# Detector.net
KiCad netlist of a schematic drawn in Altium Designer
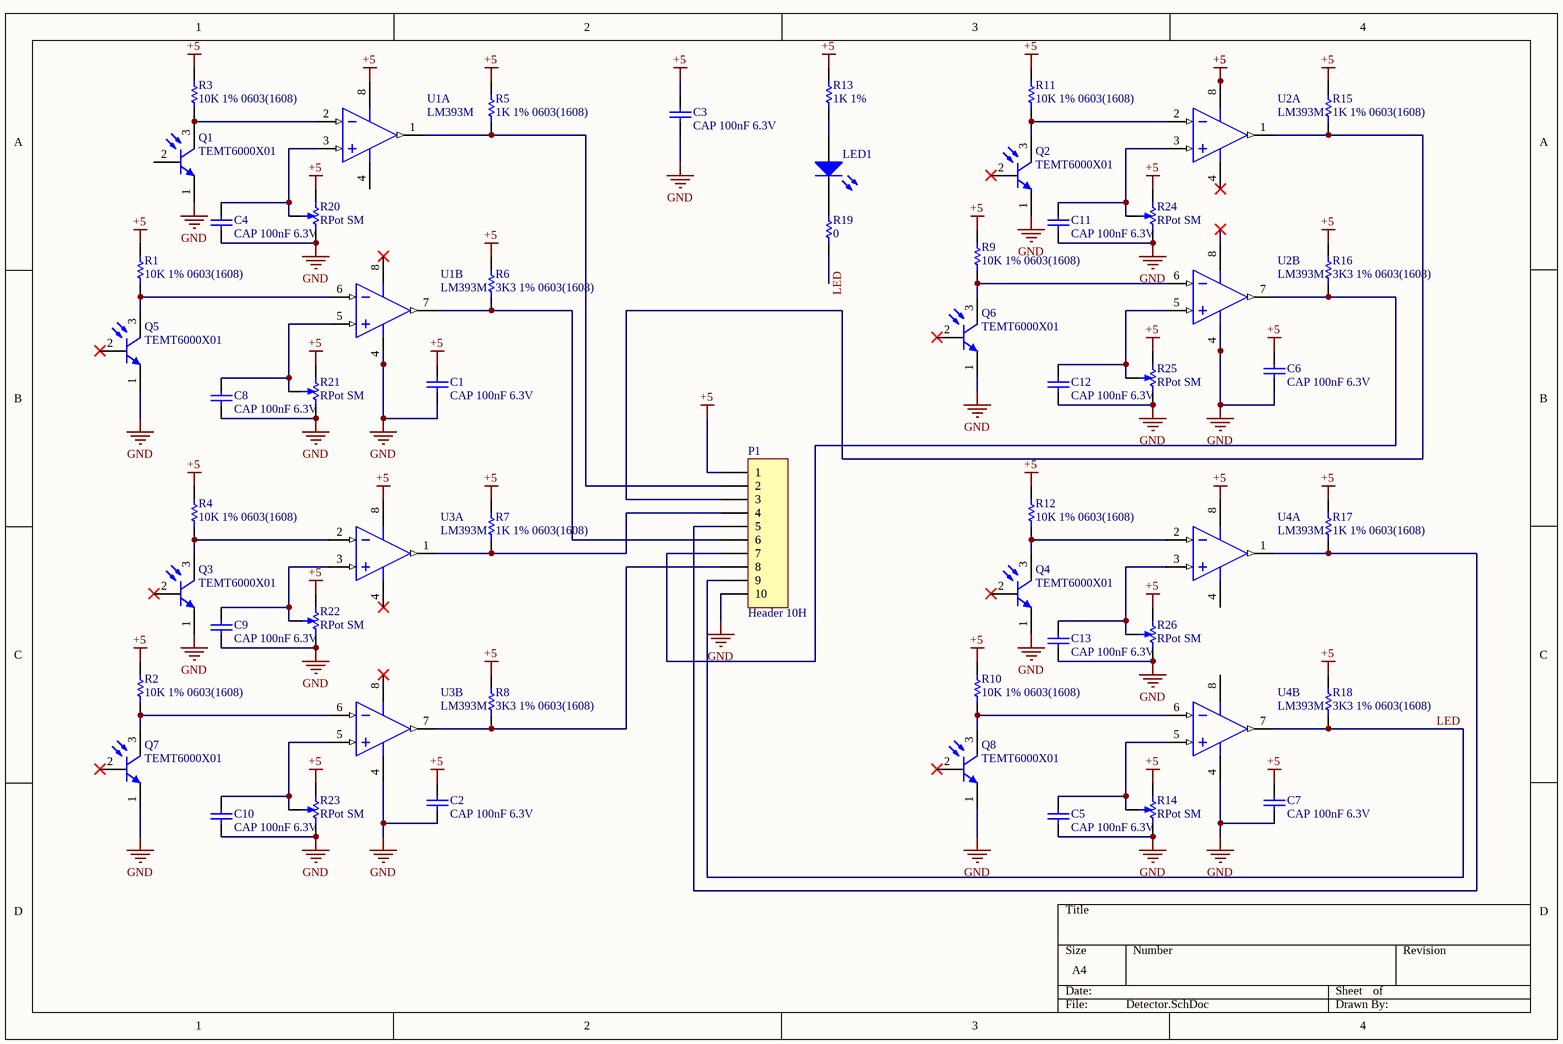
[diagram p0: Detector.SchDoc]

(export (version "E")
  (design (tool "Eeschema 10.0.6"))
  (components
    (comp (ref "C1")
      (value "CAP 100nF 6.3V")
      (footprint "CAPC0603(1608)100_N")
      (description "CAP 100nF 6.3V ±10% 0603 (1608 Metric) Thickness 1mm SMD")
      (fields (field (name "TOLERANCE") "Â±10%"))
      (libsource (lib "Altium Content Vault") (part "CAP"))
    )
    (comp (ref "C2")
      (value "CAP 100nF 6.3V")
      (footprint "CAPC0603(1608)100_N")
      (description "CAP 100nF 6.3V ±10% 0603 (1608 Metric) Thickness 1mm SMD")
      (fields (field (name "TOLERANCE") "Â±10%"))
      (libsource (lib "Altium Content Vault") (part "CAP"))
    )
    (comp (ref "C3")
      (value "CAP 100nF 6.3V")
      (footprint "CAPC0603(1608)100_N")
      (description "CAP 100nF 6.3V ±10% 0603 (1608 Metric) Thickness 1mm SMD")
      (fields (field (name "TOLERANCE") "Â±10%"))
      (libsource (lib "Altium Content Vault") (part "CAP"))
    )
    (comp (ref "C4")
      (value "CAP 100nF 6.3V")
      (footprint "CAPC0603(1608)100_N")
      (description "CAP 100nF 6.3V ±10% 0603 (1608 Metric) Thickness 1mm SMD")
      (fields (field (name "TOLERANCE") "Â±10%"))
      (libsource (lib "Altium Content Vault") (part "CAP"))
    )
    (comp (ref "C5")
      (value "CAP 100nF 6.3V")
      (footprint "CAPC0603(1608)100_N")
      (description "CAP 100nF 6.3V ±10% 0603 (1608 Metric) Thickness 1mm SMD")
      (fields (field (name "TOLERANCE") "Â±10%"))
      (libsource (lib "Altium Content Vault") (part "CAP"))
    )
    (comp (ref "C6")
      (value "CAP 100nF 6.3V")
      (footprint "CAPC0603(1608)100_N")
      (description "CAP 100nF 6.3V ±10% 0603 (1608 Metric) Thickness 1mm SMD")
      (fields (field (name "TOLERANCE") "Â±10%"))
      (libsource (lib "Altium Content Vault") (part "CAP"))
    )
    (comp (ref "C7")
      (value "CAP 100nF 6.3V")
      (footprint "CAPC0603(1608)100_N")
      (description "CAP 100nF 6.3V ±10% 0603 (1608 Metric) Thickness 1mm SMD")
      (fields (field (name "TOLERANCE") "Â±10%"))
      (libsource (lib "Altium Content Vault") (part "CAP"))
    )
    (comp (ref "C8")
      (value "CAP 100nF 6.3V")
      (footprint "CAPC0603(1608)100_N")
      (description "CAP 100nF 6.3V ±10% 0603 (1608 Metric) Thickness 1mm SMD")
      (fields (field (name "TOLERANCE") "Â±10%"))
      (libsource (lib "Altium Content Vault") (part "CAP"))
    )
    (comp (ref "C9")
      (value "CAP 100nF 6.3V")
      (footprint "CAPC0603(1608)100_N")
      (description "CAP 100nF 6.3V ±10% 0603 (1608 Metric) Thickness 1mm SMD")
      (fields (field (name "TOLERANCE") "Â±10%"))
      (libsource (lib "Altium Content Vault") (part "CAP"))
    )
    (comp (ref "C10")
      (value "CAP 100nF 6.3V")
      (footprint "CAPC0603(1608)100_N")
      (description "CAP 100nF 6.3V ±10% 0603 (1608 Metric) Thickness 1mm SMD")
      (fields (field (name "TOLERANCE") "Â±10%"))
      (libsource (lib "Altium Content Vault") (part "CAP"))
    )
    (comp (ref "C11")
      (value "CAP 100nF 6.3V")
      (footprint "CAPC0603(1608)100_N")
      (description "CAP 100nF 6.3V ±10% 0603 (1608 Metric) Thickness 1mm SMD")
      (fields (field (name "TOLERANCE") "Â±10%"))
      (libsource (lib "Altium Content Vault") (part "CAP"))
    )
    (comp (ref "C12")
      (value "CAP 100nF 6.3V")
      (footprint "CAPC0603(1608)100_N")
      (description "CAP 100nF 6.3V ±10% 0603 (1608 Metric) Thickness 1mm SMD")
      (fields (field (name "TOLERANCE") "Â±10%"))
      (libsource (lib "Altium Content Vault") (part "CAP"))
    )
    (comp (ref "C13")
      (value "CAP 100nF 6.3V")
      (footprint "CAPC0603(1608)100_N")
      (description "CAP 100nF 6.3V ±10% 0603 (1608 Metric) Thickness 1mm SMD")
      (fields (field (name "TOLERANCE") "Â±10%"))
      (libsource (lib "Altium Content Vault") (part "CAP"))
    )
    (comp (ref "LED1")
      (value "150060BS75000")
      (footprint "0603_A")
      (description "SMD mono-color Chip LED, WL-SMCW, Blue")
      (fields (field (name "MANUFACTURER") "Wuerth Elektronik"))
      (libsource (lib "Altium Content Vault") (part "WE-LED_K1A2-2"))
    )
    (comp (ref "P1")
      (value "Header 10H")
      (footprint "HDR1X10H")
      (description "Header, 10-Pin, Right Angle")
      (fields (field (name "PUBLISHER") "Altium Limited"))
      (libsource (lib "Miscellaneous Connectors") (part "Header 10H"))
    )
    (comp (ref "Q1")
      (value "TEMT6000X01")
      (footprint "VSIL-TEMT6000X01_V")
      (description "Ambient Light Sensor\r\n, 100 mW, -40 to 100 degC, 3-Pin SMD, RoHS, Tape and Reel")
      (libsource (lib "Altium Content Vault") (part "PHOTO-NPN-EBC-3"))
    )
    (comp (ref "Q2")
      (value "TEMT6000X01")
      (footprint "VSIL-TEMT6000X01_V")
      (description "Ambient Light Sensor\r\n, 100 mW, -40 to 100 degC, 3-Pin SMD, RoHS, Tape and Reel")
      (libsource (lib "Altium Content Vault") (part "PHOTO-NPN-EBC-3"))
    )
    (comp (ref "Q3")
      (value "TEMT6000X01")
      (footprint "VSIL-TEMT6000X01_V")
      (description "Ambient Light Sensor\r\n, 100 mW, -40 to 100 degC, 3-Pin SMD, RoHS, Tape and Reel")
      (libsource (lib "Altium Content Vault") (part "PHOTO-NPN-EBC-3"))
    )
    (comp (ref "Q4")
      (value "TEMT6000X01")
      (footprint "VSIL-TEMT6000X01_V")
      (description "Ambient Light Sensor\r\n, 100 mW, -40 to 100 degC, 3-Pin SMD, RoHS, Tape and Reel")
      (libsource (lib "Altium Content Vault") (part "PHOTO-NPN-EBC-3"))
    )
    (comp (ref "Q5")
      (value "TEMT6000X01")
      (footprint "VSIL-TEMT6000X01_V")
      (description "Ambient Light Sensor\r\n, 100 mW, -40 to 100 degC, 3-Pin SMD, RoHS, Tape and Reel")
      (libsource (lib "Altium Content Vault") (part "PHOTO-NPN-EBC-3"))
    )
    (comp (ref "Q6")
      (value "TEMT6000X01")
      (footprint "VSIL-TEMT6000X01_V")
      (description "Ambient Light Sensor\r\n, 100 mW, -40 to 100 degC, 3-Pin SMD, RoHS, Tape and Reel")
      (libsource (lib "Altium Content Vault") (part "PHOTO-NPN-EBC-3"))
    )
    (comp (ref "Q7")
      (value "TEMT6000X01")
      (footprint "VSIL-TEMT6000X01_V")
      (description "Ambient Light Sensor\r\n, 100 mW, -40 to 100 degC, 3-Pin SMD, RoHS, Tape and Reel")
      (libsource (lib "Altium Content Vault") (part "PHOTO-NPN-EBC-3"))
    )
    (comp (ref "Q8")
      (value "TEMT6000X01")
      (footprint "VSIL-TEMT6000X01_V")
      (description "Ambient Light Sensor\r\n, 100 mW, -40 to 100 degC, 3-Pin SMD, RoHS, Tape and Reel")
      (libsource (lib "Altium Content Vault") (part "PHOTO-NPN-EBC-3"))
    )
    (comp (ref "R1")
      (value "10K 1% 0603(1608)")
      (footprint "RESC0603(1608)_N")
      (description "10K 0.1W 1% 0603 (1608 Metric)  SMD")
      (fields (field (name "POWER") "0.1 W") (field (name "TOLERANCE") "1 %"))
      (libsource (lib "Altium Content Vault") (part "RES"))
    )
    (comp (ref "R2")
      (value "10K 1% 0603(1608)")
      (footprint "RESC0603(1608)_N")
      (description "10K 0.1W 1% 0603 (1608 Metric)  SMD")
      (fields (field (name "POWER") "0.1 W") (field (name "TOLERANCE") "1 %"))
      (libsource (lib "Altium Content Vault") (part "RES"))
    )
    (comp (ref "R3")
      (value "10K 1% 0603(1608)")
      (footprint "RESC0603(1608)_N")
      (description "10K 0.1W 1% 0603 (1608 Metric)  SMD")
      (fields (field (name "POWER") "0.1 W") (field (name "TOLERANCE") "1 %"))
      (libsource (lib "Altium Content Vault") (part "RES"))
    )
    (comp (ref "R4")
      (value "10K 1% 0603(1608)")
      (footprint "RESC0603(1608)_N")
      (description "10K 0.1W 1% 0603 (1608 Metric)  SMD")
      (fields (field (name "POWER") "0.1 W") (field (name "TOLERANCE") "1 %"))
      (libsource (lib "Altium Content Vault") (part "RES"))
    )
    (comp (ref "R5")
      (value "1K 1% 0603(1608)")
      (footprint "RESC0603(1608)_N")
      (description "3K3 0.1W 1% 0603 (1608 Metric)  SMD")
      (fields (field (name "POWER") "0.1 W") (field (name "TOLERANCE") "1 %"))
      (libsource (lib "Altium Content Vault") (part "RES"))
    )
    (comp (ref "R6")
      (value "3K3 1% 0603(1608)")
      (footprint "RESC0603(1608)_N")
      (description "3K3 0.1W 1% 0603 (1608 Metric)  SMD")
      (fields (field (name "POWER") "0.1 W") (field (name "TOLERANCE") "1 %"))
      (libsource (lib "Altium Content Vault") (part "RES"))
    )
    (comp (ref "R7")
      (value "1K 1% 0603(1608)")
      (footprint "RESC0603(1608)_N")
      (description "3K3 0.1W 1% 0603 (1608 Metric)  SMD")
      (fields (field (name "POWER") "0.1 W") (field (name "TOLERANCE") "1 %"))
      (libsource (lib "Altium Content Vault") (part "RES"))
    )
    (comp (ref "R8")
      (value "3K3 1% 0603(1608)")
      (footprint "RESC0603(1608)_N")
      (description "3K3 0.1W 1% 0603 (1608 Metric)  SMD")
      (fields (field (name "POWER") "0.1 W") (field (name "TOLERANCE") "1 %"))
      (libsource (lib "Altium Content Vault") (part "RES"))
    )
    (comp (ref "R9")
      (value "10K 1% 0603(1608)")
      (footprint "RESC0603(1608)_N")
      (description "10K 0.1W 1% 0603 (1608 Metric)  SMD")
      (fields (field (name "POWER") "0.1 W") (field (name "TOLERANCE") "1 %"))
      (libsource (lib "Altium Content Vault") (part "RES"))
    )
    (comp (ref "R10")
      (value "10K 1% 0603(1608)")
      (footprint "RESC0603(1608)_N")
      (description "10K 0.1W 1% 0603 (1608 Metric)  SMD")
      (fields (field (name "POWER") "0.1 W") (field (name "TOLERANCE") "1 %"))
      (libsource (lib "Altium Content Vault") (part "RES"))
    )
    (comp (ref "R11")
      (value "10K 1% 0603(1608)")
      (footprint "RESC0603(1608)_N")
      (description "10K 0.1W 1% 0603 (1608 Metric)  SMD")
      (fields (field (name "POWER") "0.1 W") (field (name "TOLERANCE") "1 %"))
      (libsource (lib "Altium Content Vault") (part "RES"))
    )
    (comp (ref "R12")
      (value "10K 1% 0603(1608)")
      (footprint "RESC0603(1608)_N")
      (description "10K 0.1W 1% 0603 (1608 Metric)  SMD")
      (fields (field (name "POWER") "0.1 W") (field (name "TOLERANCE") "1 %"))
      (libsource (lib "Altium Content Vault") (part "RES"))
    )
    (comp (ref "R13")
      (value "1K 1%")
      (footprint "RESC0603(1608)_N")
      (description "1K 0.1W 1% 0603 (1608 Metric)  SMD")
      (fields (field (name "TOLERANCE") "1 %") (field (name "POWER") "0.1 W"))
      (libsource (lib "Altium Content Vault") (part "RES"))
    )
    (comp (ref "R14")
      (value "RPot SM")
      (footprint "POT4MM-2")
      (description "Square Trimming Potentiometer")
      (fields (field (name "PUBLISHER") "Altium Limited"))
      (libsource (lib "Miscellaneous Devices") (part "RPot SM"))
    )
    (comp (ref "R15")
      (value "1K 1% 0603(1608)")
      (footprint "RESC0603(1608)_N")
      (description "3K3 0.1W 1% 0603 (1608 Metric)  SMD")
      (fields (field (name "POWER") "0.1 W") (field (name "TOLERANCE") "1 %"))
      (libsource (lib "Altium Content Vault") (part "RES"))
    )
    (comp (ref "R16")
      (value "3K3 1% 0603(1608)")
      (footprint "RESC0603(1608)_N")
      (description "3K3 0.1W 1% 0603 (1608 Metric)  SMD")
      (fields (field (name "POWER") "0.1 W") (field (name "TOLERANCE") "1 %"))
      (libsource (lib "Altium Content Vault") (part "RES"))
    )
    (comp (ref "R17")
      (value "1K 1% 0603(1608)")
      (footprint "RESC0603(1608)_N")
      (description "3K3 0.1W 1% 0603 (1608 Metric)  SMD")
      (fields (field (name "POWER") "0.1 W") (field (name "TOLERANCE") "1 %"))
      (libsource (lib "Altium Content Vault") (part "RES"))
    )
    (comp (ref "R18")
      (value "3K3 1% 0603(1608)")
      (footprint "RESC0603(1608)_N")
      (description "3K3 0.1W 1% 0603 (1608 Metric)  SMD")
      (fields (field (name "POWER") "0.1 W") (field (name "TOLERANCE") "1 %"))
      (libsource (lib "Altium Content Vault") (part "RES"))
    )
    (comp (ref "R19")
      (value "0")
      (footprint "RESC0603(1608)_N")
      (description "1K 0.1W 1% 0603 (1608 Metric)  SMD")
      (fields (field (name "TOLERANCE") "1 %") (field (name "POWER") "0.1 W"))
      (libsource (lib "Altium Content Vault") (part "RES"))
    )
    (comp (ref "R20")
      (value "RPot SM")
      (footprint "POT4MM-2")
      (description "Square Trimming Potentiometer")
      (fields (field (name "PUBLISHER") "Altium Limited"))
      (libsource (lib "Miscellaneous Devices") (part "RPot SM"))
    )
    (comp (ref "R21")
      (value "RPot SM")
      (footprint "POT4MM-2")
      (description "Square Trimming Potentiometer")
      (fields (field (name "PUBLISHER") "Altium Limited"))
      (libsource (lib "Miscellaneous Devices") (part "RPot SM"))
    )
    (comp (ref "R22")
      (value "RPot SM")
      (footprint "POT4MM-2")
      (description "Square Trimming Potentiometer")
      (fields (field (name "PUBLISHER") "Altium Limited"))
      (libsource (lib "Miscellaneous Devices") (part "RPot SM"))
    )
    (comp (ref "R23")
      (value "RPot SM")
      (footprint "POT4MM-2")
      (description "Square Trimming Potentiometer")
      (fields (field (name "PUBLISHER") "Altium Limited"))
      (libsource (lib "Miscellaneous Devices") (part "RPot SM"))
    )
    (comp (ref "R24")
      (value "RPot SM")
      (footprint "POT4MM-2")
      (description "Square Trimming Potentiometer")
      (fields (field (name "PUBLISHER") "Altium Limited"))
      (libsource (lib "Miscellaneous Devices") (part "RPot SM"))
    )
    (comp (ref "R25")
      (value "RPot SM")
      (footprint "POT4MM-2")
      (description "Square Trimming Potentiometer")
      (fields (field (name "PUBLISHER") "Altium Limited"))
      (libsource (lib "Miscellaneous Devices") (part "RPot SM"))
    )
    (comp (ref "R26")
      (value "RPot SM")
      (footprint "POT4MM-2")
      (description "Square Trimming Potentiometer")
      (fields (field (name "PUBLISHER") "Altium Limited"))
      (libsource (lib "Miscellaneous Devices") (part "RPot SM"))
    )
    (comp (ref "U1")
      (value "LM393M")
      (footprint "D0008A_L")
      (description "Low Power Low Offset Voltage Dual Comparator, 8-pin Narrow SOIC")
      (fields (field (name "MANUFACTURER") "Texas Instruments"))
      (libsource (lib "Altium Content Vault") (part "AN-COMP-LM193-8"))
    )
    (comp (ref "U2")
      (value "LM393M")
      (footprint "D0008A_L")
      (description "Low Power Low Offset Voltage Dual Comparator, 8-pin Narrow SOIC")
      (fields (field (name "MANUFACTURER") "Texas Instruments"))
      (libsource (lib "Altium Content Vault") (part "AN-COMP-LM193-8"))
    )
    (comp (ref "U3")
      (value "LM393M")
      (footprint "D0008A_L")
      (description "Low Power Low Offset Voltage Dual Comparator, 8-pin Narrow SOIC")
      (fields (field (name "MANUFACTURER") "Texas Instruments"))
      (libsource (lib "Altium Content Vault") (part "AN-COMP-LM193-8"))
    )
    (comp (ref "U4")
      (value "LM393M")
      (footprint "D0008A_L")
      (description "Low Power Low Offset Voltage Dual Comparator, 8-pin Narrow SOIC")
      (fields (field (name "MANUFACTURER") "Texas Instruments"))
      (libsource (lib "Altium Content Vault") (part "AN-COMP-LM193-8"))
    )
  )
  (nets
    (net (code "1") (name "+5") (class "Default")
      (node (ref "C1") (pin "2") (pinfunction "2_2") (pintype "passive"))
      (node (ref "C2") (pin "2") (pinfunction "2_2") (pintype "passive"))
      (node (ref "C3") (pin "2") (pinfunction "2_2") (pintype "passive"))
      (node (ref "C6") (pin "2") (pinfunction "2_2") (pintype "passive"))
      (node (ref "C7") (pin "2") (pinfunction "2_2") (pintype "passive"))
      (node (ref "P1") (pin "1") (pinfunction "1_1") (pintype "passive"))
      (node (ref "R1") (pin "2") (pinfunction "2_2") (pintype "passive"))
      (node (ref "R10") (pin "2") (pinfunction "2_2") (pintype "passive"))
      (node (ref "R11") (pin "2") (pinfunction "2_2") (pintype "passive"))
      (node (ref "R12") (pin "2") (pinfunction "2_2") (pintype "passive"))
      (node (ref "R13") (pin "2") (pinfunction "2_2") (pintype "passive"))
      (node (ref "R14") (pin "CCW") (pinfunction "-_CCW") (pintype "passive"))
      (node (ref "R15") (pin "2") (pinfunction "2_2") (pintype "passive"))
      (node (ref "R16") (pin "2") (pinfunction "2_2") (pintype "passive"))
      (node (ref "R17") (pin "2") (pinfunction "2_2") (pintype "passive"))
      (node (ref "R18") (pin "2") (pinfunction "2_2") (pintype "passive"))
      (node (ref "R2") (pin "2") (pinfunction "2_2") (pintype "passive"))
      (node (ref "R20") (pin "CCW") (pinfunction "-_CCW") (pintype "passive"))
      (node (ref "R21") (pin "CCW") (pinfunction "-_CCW") (pintype "passive"))
      (node (ref "R22") (pin "CCW") (pinfunction "-_CCW") (pintype "passive"))
      (node (ref "R23") (pin "CCW") (pinfunction "-_CCW") (pintype "passive"))
      (node (ref "R24") (pin "CCW") (pinfunction "-_CCW") (pintype "passive"))
      (node (ref "R25") (pin "CCW") (pinfunction "-_CCW") (pintype "passive"))
      (node (ref "R26") (pin "CCW") (pinfunction "-_CCW") (pintype "passive"))
      (node (ref "R3") (pin "2") (pinfunction "2_2") (pintype "passive"))
      (node (ref "R4") (pin "2") (pinfunction "2_2") (pintype "passive"))
      (node (ref "R5") (pin "2") (pinfunction "2_2") (pintype "passive"))
      (node (ref "R6") (pin "2") (pinfunction "2_2") (pintype "passive"))
      (node (ref "R7") (pin "2") (pinfunction "2_2") (pintype "passive"))
      (node (ref "R8") (pin "2") (pinfunction "2_2") (pintype "passive"))
      (node (ref "R9") (pin "2") (pinfunction "2_2") (pintype "passive"))
      (node (ref "U1") (pin "8") (pinfunction "V+_8") (pintype "power_in"))
      (node (ref "U2") (pin "8") (pinfunction "V+_8") (pintype "power_in"))
      (node (ref "U3") (pin "8") (pinfunction "V+_8") (pintype "power_in"))
      (node (ref "U4") (pin "8") (pinfunction "V+_8") (pintype "power_in"))
    )
    (net (code "2") (name "/LED") (class "Default")
      (node (ref "P1") (pin "9") (pinfunction "9_9") (pintype "passive"))
      (node (ref "R18") (pin "1") (pinfunction "1_1") (pintype "passive"))
      (node (ref "R19") (pin "1") (pinfunction "1_1") (pintype "passive"))
      (node (ref "U4") (pin "7") (pinfunction "OUTB_7") (pintype "output"))
    )
    (net (code "3") (name "GND") (class "Default")
      (node (ref "C1") (pin "1") (pinfunction "1_1") (pintype "passive"))
      (node (ref "C10") (pin "1") (pinfunction "1_1") (pintype "passive"))
      (node (ref "C11") (pin "1") (pinfunction "1_1") (pintype "passive"))
      (node (ref "C12") (pin "1") (pinfunction "1_1") (pintype "passive"))
      (node (ref "C13") (pin "1") (pinfunction "1_1") (pintype "passive"))
      (node (ref "C2") (pin "1") (pinfunction "1_1") (pintype "passive"))
      (node (ref "C3") (pin "1") (pinfunction "1_1") (pintype "passive"))
      (node (ref "C4") (pin "1") (pinfunction "1_1") (pintype "passive"))
      (node (ref "C5") (pin "1") (pinfunction "1_1") (pintype "passive"))
      (node (ref "C6") (pin "1") (pinfunction "1_1") (pintype "passive"))
      (node (ref "C7") (pin "1") (pinfunction "1_1") (pintype "passive"))
      (node (ref "C8") (pin "1") (pinfunction "1_1") (pintype "passive"))
      (node (ref "C9") (pin "1") (pinfunction "1_1") (pintype "passive"))
      (node (ref "P1") (pin "10") (pinfunction "10_10") (pintype "passive"))
      (node (ref "Q1") (pin "1") (pinfunction "E_1") (pintype "passive"))
      (node (ref "Q2") (pin "1") (pinfunction "E_1") (pintype "passive"))
      (node (ref "Q3") (pin "1") (pinfunction "E_1") (pintype "passive"))
      (node (ref "Q4") (pin "1") (pinfunction "E_1") (pintype "passive"))
      (node (ref "Q5") (pin "1") (pinfunction "E_1") (pintype "passive"))
      (node (ref "Q6") (pin "1") (pinfunction "E_1") (pintype "passive"))
      (node (ref "Q7") (pin "1") (pinfunction "E_1") (pintype "passive"))
      (node (ref "Q8") (pin "1") (pinfunction "E_1") (pintype "passive"))
      (node (ref "R14") (pin "CW") (pinfunction "+_CW") (pintype "passive"))
      (node (ref "R20") (pin "CW") (pinfunction "+_CW") (pintype "passive"))
      (node (ref "R21") (pin "CW") (pinfunction "+_CW") (pintype "passive"))
      (node (ref "R22") (pin "CW") (pinfunction "+_CW") (pintype "passive"))
      (node (ref "R23") (pin "CW") (pinfunction "+_CW") (pintype "passive"))
      (node (ref "R24") (pin "CW") (pinfunction "+_CW") (pintype "passive"))
      (node (ref "R25") (pin "CW") (pinfunction "+_CW") (pintype "passive"))
      (node (ref "R26") (pin "CW") (pinfunction "+_CW") (pintype "passive"))
      (node (ref "U1") (pin "4") (pinfunction "GND_4") (pintype "power_in"))
      (node (ref "U2") (pin "4") (pinfunction "GND_4") (pintype "power_in"))
      (node (ref "U3") (pin "4") (pinfunction "GND_4") (pintype "power_in"))
      (node (ref "U4") (pin "4") (pinfunction "GND_4") (pintype "power_in"))
    )
    (net (code "4") (name "Net-(LED1-A)") (class "Default")
      (node (ref "LED1") (pin "2") (pinfunction "A_2") (pintype "passive"))
      (node (ref "R13") (pin "1") (pinfunction "1_1") (pintype "passive"))
    )
    (net (code "5") (name "Net-(LED1-K)") (class "Default")
      (node (ref "LED1") (pin "1") (pinfunction "K_1") (pintype "passive"))
      (node (ref "R19") (pin "2") (pinfunction "2_2") (pintype "passive"))
    )
    (net (code "6") (name "Net-(Q1-C)") (class "Default")
      (node (ref "Q1") (pin "3") (pinfunction "C_3") (pintype "passive"))
      (node (ref "R3") (pin "1") (pinfunction "1_1") (pintype "passive"))
      (node (ref "U1") (pin "2") (pinfunction "INA-_2") (pintype "input"))
    )
    (net (code "7") (name "Net-(Q2-C)") (class "Default")
      (node (ref "Q2") (pin "3") (pinfunction "C_3") (pintype "passive"))
      (node (ref "R11") (pin "1") (pinfunction "1_1") (pintype "passive"))
      (node (ref "U2") (pin "2") (pinfunction "INA-_2") (pintype "input"))
    )
    (net (code "8") (name "Net-(Q3-C)") (class "Default")
      (node (ref "Q3") (pin "3") (pinfunction "C_3") (pintype "passive"))
      (node (ref "R4") (pin "1") (pinfunction "1_1") (pintype "passive"))
      (node (ref "U3") (pin "2") (pinfunction "INA-_2") (pintype "input"))
    )
    (net (code "9") (name "Net-(Q4-C)") (class "Default")
      (node (ref "Q4") (pin "3") (pinfunction "C_3") (pintype "passive"))
      (node (ref "R12") (pin "1") (pinfunction "1_1") (pintype "passive"))
      (node (ref "U4") (pin "2") (pinfunction "INA-_2") (pintype "input"))
    )
    (net (code "10") (name "Net-(Q5-C)") (class "Default")
      (node (ref "Q5") (pin "3") (pinfunction "C_3") (pintype "passive"))
      (node (ref "R1") (pin "1") (pinfunction "1_1") (pintype "passive"))
      (node (ref "U1") (pin "6") (pinfunction "INB-_6") (pintype "input"))
    )
    (net (code "11") (name "Net-(Q6-C)") (class "Default")
      (node (ref "Q6") (pin "3") (pinfunction "C_3") (pintype "passive"))
      (node (ref "R9") (pin "1") (pinfunction "1_1") (pintype "passive"))
      (node (ref "U2") (pin "6") (pinfunction "INB-_6") (pintype "input"))
    )
    (net (code "12") (name "Net-(Q7-C)") (class "Default")
      (node (ref "Q7") (pin "3") (pinfunction "C_3") (pintype "passive"))
      (node (ref "R2") (pin "1") (pinfunction "1_1") (pintype "passive"))
      (node (ref "U3") (pin "6") (pinfunction "INB-_6") (pintype "input"))
    )
    (net (code "13") (name "Net-(Q8-C)") (class "Default")
      (node (ref "Q8") (pin "3") (pinfunction "C_3") (pintype "passive"))
      (node (ref "R10") (pin "1") (pinfunction "1_1") (pintype "passive"))
      (node (ref "U4") (pin "6") (pinfunction "INB-_6") (pintype "input"))
    )
    (net (code "14") (name "Net-(U1A-INA+)") (class "Default")
      (node (ref "C4") (pin "2") (pinfunction "2_2") (pintype "passive"))
      (node (ref "R20") (pin "W") (pinfunction "W_W") (pintype "passive"))
      (node (ref "U1") (pin "3") (pinfunction "INA+_3") (pintype "input"))
    )
    (net (code "15") (name "Net-(U1A-OUTA)") (class "Default")
      (node (ref "P1") (pin "2") (pinfunction "2_2") (pintype "passive"))
      (node (ref "R5") (pin "1") (pinfunction "1_1") (pintype "passive"))
      (node (ref "U1") (pin "1") (pinfunction "OUTA_1") (pintype "output"))
    )
    (net (code "16") (name "Net-(U1B-INB+)") (class "Default")
      (node (ref "C8") (pin "2") (pinfunction "2_2") (pintype "passive"))
      (node (ref "R21") (pin "W") (pinfunction "W_W") (pintype "passive"))
      (node (ref "U1") (pin "5") (pinfunction "INB+_5") (pintype "input"))
    )
    (net (code "17") (name "Net-(U1B-OUTB)") (class "Default")
      (node (ref "P1") (pin "6") (pinfunction "6_6") (pintype "passive"))
      (node (ref "R6") (pin "1") (pinfunction "1_1") (pintype "passive"))
      (node (ref "U1") (pin "7") (pinfunction "OUTB_7") (pintype "output"))
    )
    (net (code "18") (name "Net-(U2A-INA+)") (class "Default")
      (node (ref "C11") (pin "2") (pinfunction "2_2") (pintype "passive"))
      (node (ref "R24") (pin "W") (pinfunction "W_W") (pintype "passive"))
      (node (ref "U2") (pin "3") (pinfunction "INA+_3") (pintype "input"))
    )
    (net (code "19") (name "Net-(U2A-OUTA)") (class "Default")
      (node (ref "P1") (pin "3") (pinfunction "3_3") (pintype "passive"))
      (node (ref "R15") (pin "1") (pinfunction "1_1") (pintype "passive"))
      (node (ref "U2") (pin "1") (pinfunction "OUTA_1") (pintype "output"))
    )
    (net (code "20") (name "Net-(U2B-INB+)") (class "Default")
      (node (ref "C12") (pin "2") (pinfunction "2_2") (pintype "passive"))
      (node (ref "R25") (pin "W") (pinfunction "W_W") (pintype "passive"))
      (node (ref "U2") (pin "5") (pinfunction "INB+_5") (pintype "input"))
    )
    (net (code "21") (name "Net-(U2B-OUTB)") (class "Default")
      (node (ref "P1") (pin "7") (pinfunction "7_7") (pintype "passive"))
      (node (ref "R16") (pin "1") (pinfunction "1_1") (pintype "passive"))
      (node (ref "U2") (pin "7") (pinfunction "OUTB_7") (pintype "output"))
    )
    (net (code "22") (name "Net-(U3A-INA+)") (class "Default")
      (node (ref "C9") (pin "2") (pinfunction "2_2") (pintype "passive"))
      (node (ref "R22") (pin "W") (pinfunction "W_W") (pintype "passive"))
      (node (ref "U3") (pin "3") (pinfunction "INA+_3") (pintype "input"))
    )
    (net (code "23") (name "Net-(U3A-OUTA)") (class "Default")
      (node (ref "P1") (pin "4") (pinfunction "4_4") (pintype "passive"))
      (node (ref "R7") (pin "1") (pinfunction "1_1") (pintype "passive"))
      (node (ref "U3") (pin "1") (pinfunction "OUTA_1") (pintype "output"))
    )
    (net (code "24") (name "Net-(U3B-INB+)") (class "Default")
      (node (ref "C10") (pin "2") (pinfunction "2_2") (pintype "passive"))
      (node (ref "R23") (pin "W") (pinfunction "W_W") (pintype "passive"))
      (node (ref "U3") (pin "5") (pinfunction "INB+_5") (pintype "input"))
    )
    (net (code "25") (name "Net-(U3B-OUTB)") (class "Default")
      (node (ref "P1") (pin "8") (pinfunction "8_8") (pintype "passive"))
      (node (ref "R8") (pin "1") (pinfunction "1_1") (pintype "passive"))
      (node (ref "U3") (pin "7") (pinfunction "OUTB_7") (pintype "output"))
    )
    (net (code "26") (name "Net-(U4A-INA+)") (class "Default")
      (node (ref "C13") (pin "2") (pinfunction "2_2") (pintype "passive"))
      (node (ref "R26") (pin "W") (pinfunction "W_W") (pintype "passive"))
      (node (ref "U4") (pin "3") (pinfunction "INA+_3") (pintype "input"))
    )
    (net (code "27") (name "Net-(U4A-OUTA)") (class "Default")
      (node (ref "P1") (pin "5") (pinfunction "5_5") (pintype "passive"))
      (node (ref "R17") (pin "1") (pinfunction "1_1") (pintype "passive"))
      (node (ref "U4") (pin "1") (pinfunction "OUTA_1") (pintype "output"))
    )
    (net (code "28") (name "Net-(U4B-INB+)") (class "Default")
      (node (ref "C5") (pin "2") (pinfunction "2_2") (pintype "passive"))
      (node (ref "R14") (pin "W") (pinfunction "W_W") (pintype "passive"))
      (node (ref "U4") (pin "5") (pinfunction "INB+_5") (pintype "input"))
    )
    (net (code "29") (name "unconnected-(Q1-B-Pad2)") (class "Default")
      (node (ref "Q1") (pin "2") (pinfunction "B_2") (pintype "passive"))
    )
    (net (code "30") (name "unconnected-(Q2-B-Pad2)") (class "Default")
      (node (ref "Q2") (pin "2") (pinfunction "B_2") (pintype "passive+no_connect"))
    )
    (net (code "31") (name "unconnected-(Q3-B-Pad2)") (class "Default")
      (node (ref "Q3") (pin "2") (pinfunction "B_2") (pintype "passive+no_connect"))
    )
    (net (code "32") (name "unconnected-(Q4-B-Pad2)") (class "Default")
      (node (ref "Q4") (pin "2") (pinfunction "B_2") (pintype "passive+no_connect"))
    )
    (net (code "33") (name "unconnected-(Q5-B-Pad2)") (class "Default")
      (node (ref "Q5") (pin "2") (pinfunction "B_2") (pintype "passive+no_connect"))
    )
    (net (code "34") (name "unconnected-(Q6-B-Pad2)") (class "Default")
      (node (ref "Q6") (pin "2") (pinfunction "B_2") (pintype "passive+no_connect"))
    )
    (net (code "35") (name "unconnected-(Q7-B-Pad2)") (class "Default")
      (node (ref "Q7") (pin "2") (pinfunction "B_2") (pintype "passive+no_connect"))
    )
    (net (code "36") (name "unconnected-(Q8-B-Pad2)") (class "Default")
      (node (ref "Q8") (pin "2") (pinfunction "B_2") (pintype "passive+no_connect"))
    )
    (net (code "37") (name "unconnected-(U1A-GND-Pad4)") (class "Default")
      (node (ref "U1") (pin "4") (pinfunction "GND_4") (pintype "power_in"))
    )
    (net (code "38") (name "unconnected-(U1B-V+-Pad8)") (class "Default")
      (node (ref "U1") (pin "8") (pinfunction "V+_8") (pintype "power_in+no_connect"))
    )
    (net (code "39") (name "unconnected-(U2A-GND-Pad4)") (class "Default")
      (node (ref "U2") (pin "4") (pinfunction "GND_4") (pintype "power_in+no_connect"))
    )
    (net (code "40") (name "unconnected-(U2B-V+-Pad8)") (class "Default")
      (node (ref "U2") (pin "8") (pinfunction "V+_8") (pintype "power_in+no_connect"))
    )
    (net (code "41") (name "unconnected-(U3A-GND-Pad4)") (class "Default")
      (node (ref "U3") (pin "4") (pinfunction "GND_4") (pintype "power_in+no_connect"))
    )
    (net (code "42") (name "unconnected-(U3B-V+-Pad8)") (class "Default")
      (node (ref "U3") (pin "8") (pinfunction "V+_8") (pintype "power_in+no_connect"))
    )
    (net (code "43") (name "unconnected-(U4A-GND-Pad4)") (class "Default")
      (node (ref "U4") (pin "4") (pinfunction "GND_4") (pintype "power_in"))
    )
    (net (code "44") (name "unconnected-(U4B-V+-Pad8)") (class "Default")
      (node (ref "U4") (pin "8") (pinfunction "V+_8") (pintype "power_in"))
    )
  )
)
